# Adafruit_Trinket_5V_microUSB.net
KiCad netlist of a schematic drawn in EAGLE
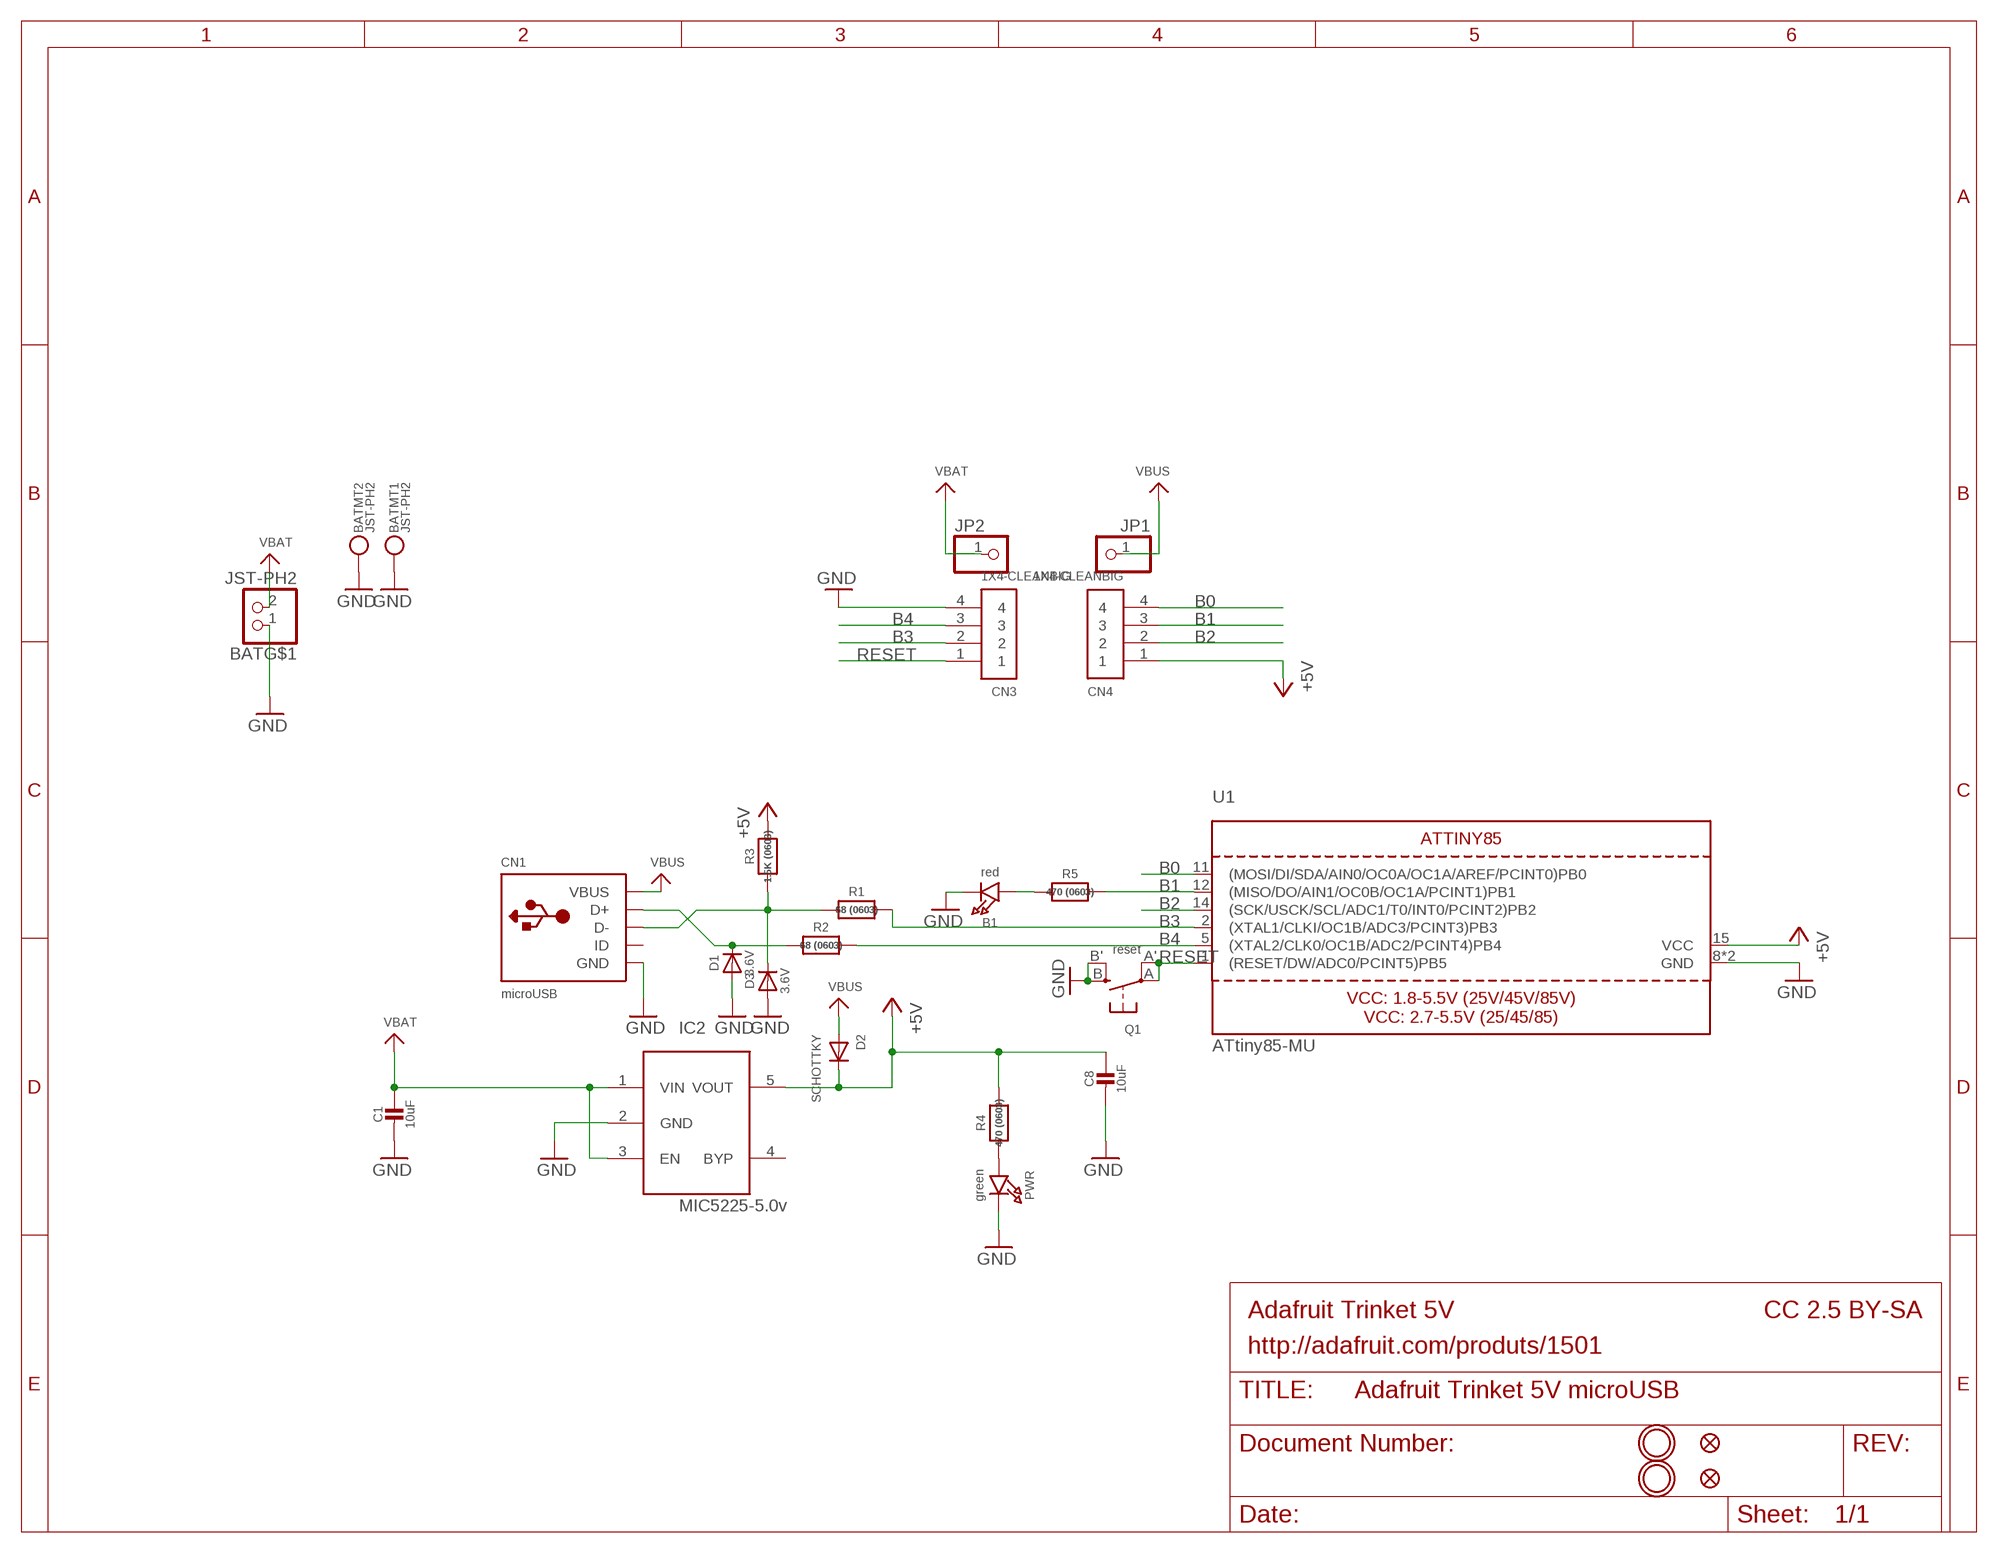
[diagram p0: schematic, sheet 1]

(export (version "E")
  (design (tool "Eeschema 10.0.6"))
  (components
    (comp (ref "B1")
      (value "red")
      (footprint "eagle-import:CHIPLED_0805_NOOUTLINE")
      (libsource (lib "eagle-import") (part "LED0805_NOOUTLINE"))
    )
    (comp (ref "BAT")
      (value "JST-PH2")
      (footprint "eagle-import:JSTPH2")
      (libsource (lib "eagle-import") (part "CON_JST_PH_2PIN_MTPH2"))
    )
    (comp (ref "C1")
      (value "10uF")
      (footprint "eagle-import:0805-NO")
      (libsource (lib "eagle-import") (part "CAP_CERAMIC0805-NOOUTLINE"))
    )
    (comp (ref "C8")
      (value "10uF")
      (footprint "eagle-import:0805-NO")
      (libsource (lib "eagle-import") (part "CAP_CERAMIC0805-NOOUTLINE"))
    )
    (comp (ref "CN1")
      (value "microUSB")
      (footprint "eagle-import:4UCONN_20329")
      (libsource (lib "eagle-import") (part "USBMICRO_20329"))
    )
    (comp (ref "CN3")
      (value "1X4-CLEANBIG")
      (footprint "eagle-import:1X04-CLEANBIG")
      (libsource (lib "eagle-import") (part "1X4-CLEANBIG"))
    )
    (comp (ref "CN4")
      (value "1X4-CLEANBIG")
      (footprint "eagle-import:1X04-CLEANBIG")
      (libsource (lib "eagle-import") (part "1X4-CLEANBIG"))
    )
    (comp (ref "D1")
      (value "3.6V")
      (footprint "eagle-import:SOD-323")
      (libsource (lib "eagle-import") (part "DIODESOD-323"))
    )
    (comp (ref "D2")
      (value "SCHOTTKY")
      (footprint "eagle-import:SOD-123FL")
      (libsource (lib "eagle-import") (part "DIODE_SOD-123FL"))
    )
    (comp (ref "D3")
      (value "3.6V")
      (footprint "eagle-import:SOD-323")
      (libsource (lib "eagle-import") (part "DIODESOD-323"))
    )
    (comp (ref "IC2")
      (value "MIC5225-5.0v")
      (footprint "eagle-import:SOT23-5L")
      (libsource (lib "eagle-import") (part "LP298XS"))
    )
    (comp (ref "JP1")
      (value "PINHD-1X1CB")
      (footprint "eagle-import:1X01-CLEANBIG")
      (libsource (lib "eagle-import") (part "PINHD-1X1CB"))
    )
    (comp (ref "JP2")
      (value "PINHD-1X1CB")
      (footprint "eagle-import:1X01-CLEANBIG")
      (libsource (lib "eagle-import") (part "PINHD-1X1CB"))
    )
    (comp (ref "PWR")
      (value "green")
      (footprint "eagle-import:CHIPLED_0805_NOOUTLINE")
      (libsource (lib "eagle-import") (part "LED0805_NOOUTLINE"))
    )
    (comp (ref "Q1")
      (value "reset")
      (footprint "eagle-import:BTN_KMR2_4.6X2.8")
      (libsource (lib "eagle-import") (part "SWITCH_TACT_SMT4.6X2.8"))
    )
    (comp (ref "R1")
      (value "68 (0603)")
      (footprint "eagle-import:0603-NO")
      (libsource (lib "eagle-import") (part "RESISTOR_0603_NOOUT"))
    )
    (comp (ref "R2")
      (value "68 (0603)")
      (footprint "eagle-import:0603-NO")
      (libsource (lib "eagle-import") (part "RESISTOR_0603_NOOUT"))
    )
    (comp (ref "R3")
      (value "1.5K (0603)")
      (footprint "eagle-import:0603-NO")
      (libsource (lib "eagle-import") (part "RESISTOR_0603_NOOUT"))
    )
    (comp (ref "R4")
      (value "470 (0603)")
      (footprint "eagle-import:0603-NO")
      (libsource (lib "eagle-import") (part "RESISTOR_0603_NOOUT"))
    )
    (comp (ref "R5")
      (value "470 (0603)")
      (footprint "eagle-import:0603-NO")
      (libsource (lib "eagle-import") (part "RESISTOR_0603_NOOUT"))
    )
    (comp (ref "U$1")
      (value "FIDUCIAL\"\"")
      (footprint "eagle-import:FIDUCIAL_1MM")
      (libsource (lib "eagle-import") (part "FIDUCIAL{dblquote}{dblquote}"))
    )
    (comp (ref "U$6")
      (value "FIDUCIAL\"\"")
      (footprint "eagle-import:FIDUCIAL_1MM")
      (libsource (lib "eagle-import") (part "FIDUCIAL{dblquote}{dblquote}"))
    )
    (comp (ref "U$8")
      (value "MOUNTINGHOLE2.0")
      (footprint "eagle-import:MOUNTINGHOLE_2.0_PLATED")
      (libsource (lib "eagle-import") (part "MOUNTINGHOLE2.0"))
    )
    (comp (ref "U$9")
      (value "MOUNTINGHOLE2.0")
      (footprint "eagle-import:MOUNTINGHOLE_2.0_PLATED")
      (libsource (lib "eagle-import") (part "MOUNTINGHOLE2.0"))
    )
    (comp (ref "U1")
      (value "ATtiny85-MU")
      (footprint "eagle-import:MLF20_4X4MM_0.5MM_ATMEL")
      (libsource (lib "eagle-import") (part "ATTINY85"))
    )
  )
  (nets
    (net (code "1") (name "+5V") (class "Default")
      (node (ref "C8") (pin "1") (pinfunction "1_1") (pintype "passive"))
      (node (ref "CN4") (pin "1") (pinfunction "1_1") (pintype "bidirectional"))
      (node (ref "D2") (pin "C") (pinfunction "C_C") (pintype "passive"))
      (node (ref "IC2") (pin "5") (pinfunction "VOUT_5") (pintype "bidirectional"))
      (node (ref "R3") (pin "2") (pinfunction "2_2") (pintype "passive"))
      (node (ref "R4") (pin "2") (pinfunction "2_2") (pintype "passive"))
      (node (ref "U1") (pin "15") (pinfunction "VCC_15") (pintype "power_in"))
    )
    (net (code "2") (name "/B0") (class "Default")
      (node (ref "CN4") (pin "4") (pinfunction "4_4") (pintype "bidirectional"))
      (node (ref "U1") (pin "11") (pinfunction "(MOSI/DI/SDA/AIN0/OC0A/OC1A/AREF/PCINT0)PB0_11") (pintype "bidirectional"))
    )
    (net (code "3") (name "/B1") (class "Default")
      (node (ref "CN4") (pin "3") (pinfunction "3_3") (pintype "bidirectional"))
      (node (ref "R5") (pin "2") (pinfunction "2_2") (pintype "passive"))
      (node (ref "U1") (pin "12") (pinfunction "(MISO/DO/AIN1/OC0B/OC1A/PCINT1)PB1_12") (pintype "bidirectional"))
    )
    (net (code "4") (name "/B2") (class "Default")
      (node (ref "CN4") (pin "2") (pinfunction "2_2") (pintype "bidirectional"))
      (node (ref "U1") (pin "14") (pinfunction "(SCK/USCK/SCL/ADC1/T0/INT0/PCINT2)PB2_14") (pintype "bidirectional"))
    )
    (net (code "5") (name "/B3") (class "Default")
      (node (ref "CN3") (pin "2") (pinfunction "2_2") (pintype "bidirectional"))
      (node (ref "R1") (pin "2") (pinfunction "2_2") (pintype "passive"))
      (node (ref "U1") (pin "2") (pinfunction "(XTAL1/CLKI/OC1B/ADC3/PCINT3)PB3_2") (pintype "bidirectional"))
    )
    (net (code "6") (name "/B4") (class "Default")
      (node (ref "CN3") (pin "3") (pinfunction "3_3") (pintype "bidirectional"))
      (node (ref "R2") (pin "2") (pinfunction "2_2") (pintype "passive"))
      (node (ref "U1") (pin "5") (pinfunction "(XTAL2/CLK0/OC1B/ADC2/PCINT4)PB4_5") (pintype "bidirectional"))
    )
    (net (code "7") (name "/RESET") (class "Default")
      (node (ref "CN3") (pin "1") (pinfunction "1_1") (pintype "bidirectional"))
      (node (ref "Q1") (pin "A") (pinfunction "P_A") (pintype "passive"))
      (node (ref "Q1") (pin "A'") (pinfunction "P1_A'") (pintype "passive"))
      (node (ref "U1") (pin "1") (pinfunction "(RESET/DW/ADC0/PCINT5)PB5_1") (pintype "bidirectional"))
    )
    (net (code "8") (name "GND") (class "Default")
      (node (ref "B1") (pin "C") (pinfunction "C_C") (pintype "passive"))
      (node (ref "BAT") (pin "1") (pinfunction "1_1") (pintype "passive"))
      (node (ref "BAT") (pin "NC1") (pinfunction "P$1_NC1") (pintype "bidirectional"))
      (node (ref "BAT") (pin "NC2") (pinfunction "P$1_NC2") (pintype "bidirectional"))
      (node (ref "C1") (pin "2") (pinfunction "2_2") (pintype "passive"))
      (node (ref "C8") (pin "2") (pinfunction "2_2") (pintype "passive"))
      (node (ref "CN1") (pin "BASE@1") (pinfunction "GND_BASE@1") (pintype "power_in"))
      (node (ref "CN1") (pin "BASE@2") (pinfunction "GND_BASE@2") (pintype "power_in"))
      (node (ref "CN1") (pin "GND") (pinfunction "GND_GND") (pintype "power_in"))
      (node (ref "CN1") (pin "SPRT@1") (pinfunction "GND_SPRT@1") (pintype "power_in"))
      (node (ref "CN1") (pin "SPRT@2") (pinfunction "GND_SPRT@2") (pintype "power_in"))
      (node (ref "CN1") (pin "SPRT@3") (pinfunction "GND_SPRT@3") (pintype "power_in"))
      (node (ref "CN1") (pin "SPRT@4") (pinfunction "GND_SPRT@4") (pintype "power_in"))
      (node (ref "CN3") (pin "4") (pinfunction "4_4") (pintype "bidirectional"))
      (node (ref "D1") (pin "A") (pinfunction "A_A") (pintype "passive"))
      (node (ref "D3") (pin "A") (pinfunction "A_A") (pintype "passive"))
      (node (ref "IC2") (pin "2") (pinfunction "GND_2") (pintype "bidirectional"))
      (node (ref "PWR") (pin "C") (pinfunction "C_C") (pintype "passive"))
      (node (ref "Q1") (pin "B") (pinfunction "S_B") (pintype "passive"))
      (node (ref "Q1") (pin "B'") (pinfunction "S1_B'") (pintype "passive"))
      (node (ref "U1") (pin "8") (pinfunction "GND_8") (pintype "power_in"))
      (node (ref "U1") (pin "THERMAL") (pinfunction "GND_THERMAL") (pintype "power_in"))
    )
    (net (code "9") (name "Net-(B1-PadA)") (class "Default")
      (node (ref "B1") (pin "A") (pinfunction "A_A") (pintype "passive"))
      (node (ref "R5") (pin "1") (pinfunction "1_1") (pintype "passive"))
    )
    (net (code "10") (name "Net-(CN1-PadD+)") (class "Default")
      (node (ref "CN1") (pin "D+") (pinfunction "D+_D+") (pintype "bidirectional"))
      (node (ref "D1") (pin "C") (pinfunction "C_C") (pintype "passive"))
      (node (ref "R2") (pin "1") (pinfunction "1_1") (pintype "passive"))
    )
    (net (code "11") (name "Net-(CN1-PadD-)") (class "Default")
      (node (ref "CN1") (pin "D-") (pinfunction "D-_D-") (pintype "bidirectional"))
      (node (ref "D3") (pin "C") (pinfunction "C_C") (pintype "passive"))
      (node (ref "R1") (pin "1") (pinfunction "1_1") (pintype "passive"))
      (node (ref "R3") (pin "1") (pinfunction "1_1") (pintype "passive"))
    )
    (net (code "12") (name "Net-(PWR-PadA)") (class "Default")
      (node (ref "PWR") (pin "A") (pinfunction "A_A") (pintype "passive"))
      (node (ref "R4") (pin "1") (pinfunction "1_1") (pintype "passive"))
    )
    (net (code "13") (name "VBAT") (class "Default")
      (node (ref "BAT") (pin "2") (pinfunction "2_2") (pintype "passive"))
      (node (ref "C1") (pin "1") (pinfunction "1_1") (pintype "passive"))
      (node (ref "IC2") (pin "1") (pinfunction "VIN_1") (pintype "bidirectional"))
      (node (ref "IC2") (pin "3") (pinfunction "EN_3") (pintype "bidirectional"))
      (node (ref "JP2") (pin "1") (pinfunction "1_1") (pintype "passive"))
    )
    (net (code "14") (name "VBUS") (class "Default")
      (node (ref "CN1") (pin "VBUS") (pinfunction "VBUS_VBUS") (pintype "power_in"))
      (node (ref "D2") (pin "A") (pinfunction "A_A") (pintype "passive"))
      (node (ref "JP1") (pin "1") (pinfunction "1_1") (pintype "passive"))
    )
    (net (code "15") (name "unconnected-(CN1-PadID)") (class "Default")
      (node (ref "CN1") (pin "ID") (pinfunction "ID_ID") (pintype "bidirectional"))
    )
    (net (code "16") (name "unconnected-(IC2-BYP-Pad4)") (class "Default")
      (node (ref "IC2") (pin "4") (pinfunction "BYP_4") (pintype "bidirectional"))
    )
  )
)
